# ProProject_3StepperShield_2024-04-21.net
KiCad netlist of a schematic drawn in EasyEDA Pro
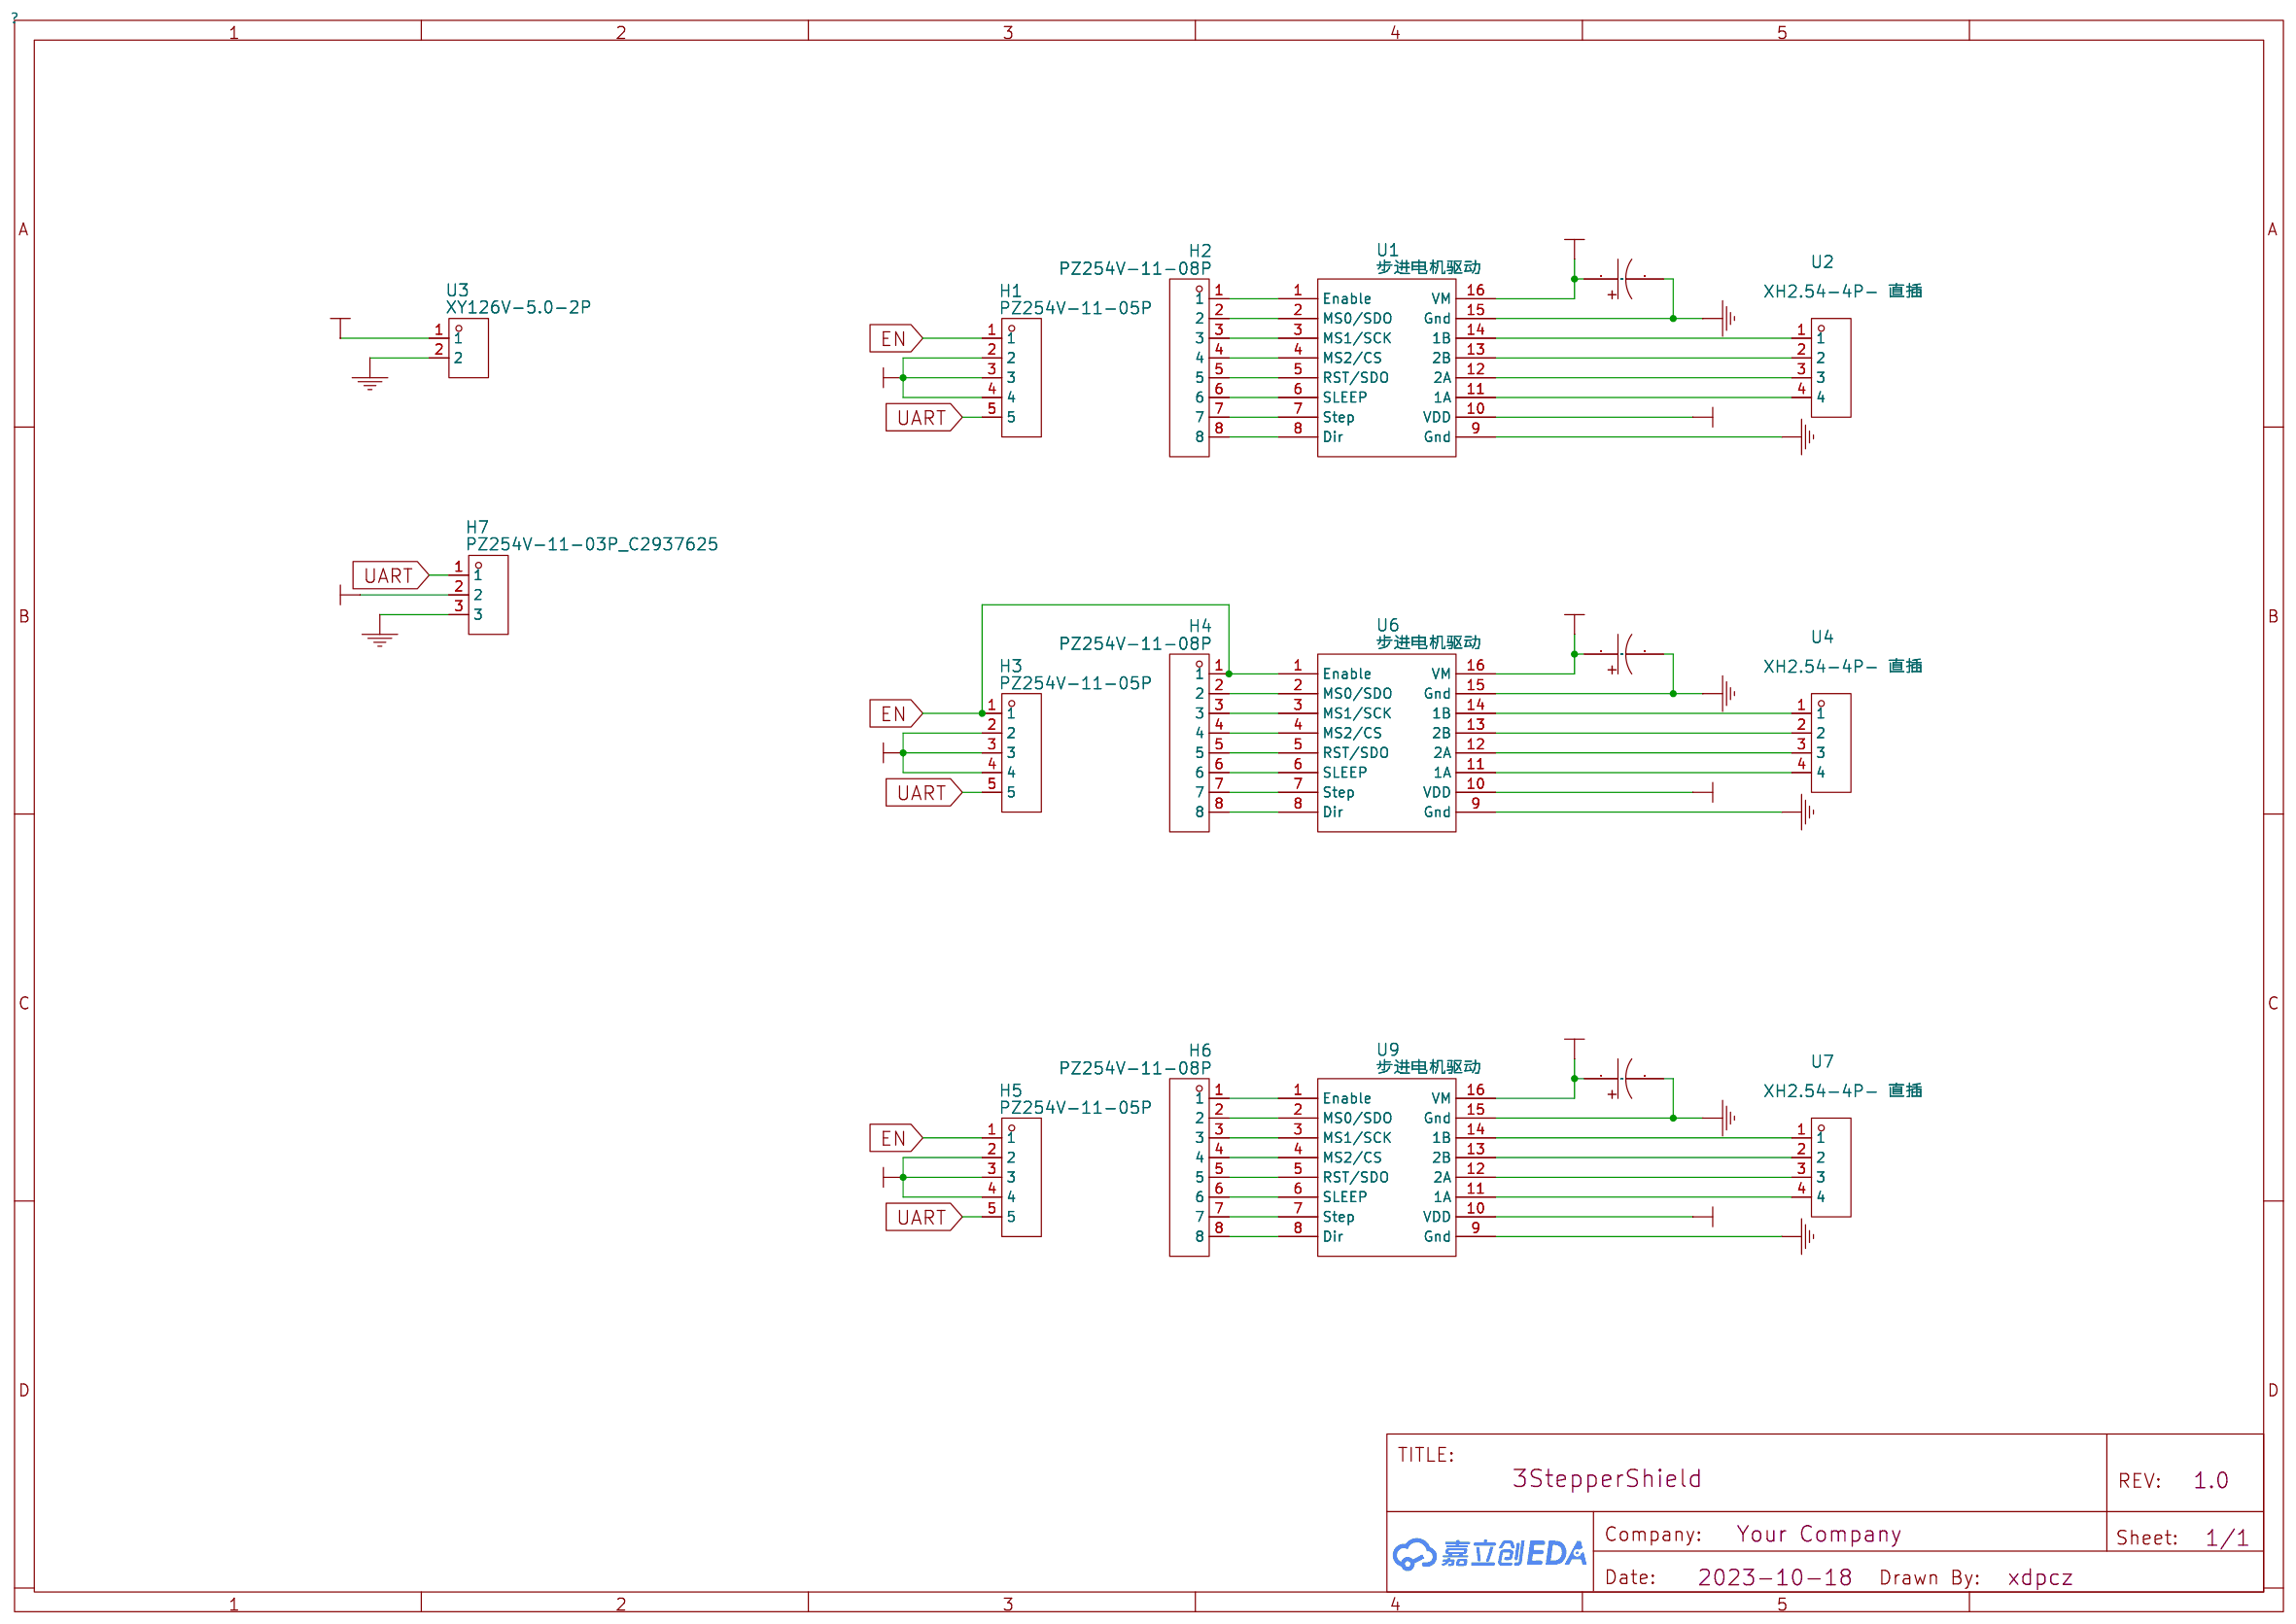
[diagram p0: schematic sheet]

(export (version "E")
  (design (tool "Eeschema 10.0.6"))
  (components
    (comp (ref "H1")
      (value "PZ254V-11-05P")
      (footprint "easyedapro:HDR-TH_5P-P2.54-V-M")
      (fields (field (name "Manufacturer") "XFCN(兴飞)"))
      (libsource (lib "easyedapro") (part "PZ254V-11-05P"))
    )
    (comp (ref "H2")
      (value "PZ254V-11-08P")
      (footprint "easyedapro:HDR-TH_8P-P2.54-V-M")
      (fields (field (name "Manufacturer") "XFCN(兴飞)"))
      (libsource (lib "easyedapro") (part "PZ254V-11-08P"))
    )
    (comp (ref "H3")
      (value "PZ254V-11-05P")
      (footprint "easyedapro:HDR-TH_5P-P2.54-V-M")
      (fields (field (name "Manufacturer") "XFCN(兴飞)"))
      (libsource (lib "easyedapro") (part "PZ254V-11-05P"))
    )
    (comp (ref "H4")
      (value "PZ254V-11-08P")
      (footprint "easyedapro:HDR-TH_8P-P2.54-V-M")
      (fields (field (name "Manufacturer") "XFCN(兴飞)"))
      (libsource (lib "easyedapro") (part "PZ254V-11-08P"))
    )
    (comp (ref "H5")
      (value "PZ254V-11-05P")
      (footprint "easyedapro:HDR-TH_5P-P2.54-V-M")
      (fields (field (name "Manufacturer") "XFCN(兴飞)"))
      (libsource (lib "easyedapro") (part "PZ254V-11-05P"))
    )
    (comp (ref "H6")
      (value "PZ254V-11-08P")
      (footprint "easyedapro:HDR-TH_8P-P2.54-V-M")
      (fields (field (name "Manufacturer") "XFCN(兴飞)"))
      (libsource (lib "easyedapro") (part "PZ254V-11-08P"))
    )
    (comp (ref "H7")
      (value "PZ254V-11-03P_C2937625")
      (footprint "easyedapro:HDR-TH_3P-P2.54-V-M")
      (fields (field (name "Manufacturer Part") "PZ254V-11-03P") (field (name "Manufacturer") "XFCN(兴飞)"))
      (libsource (lib "easyedapro") (part "PZ254V-11-03P_C2937625"))
    )
    (comp (ref "U1")
      (value "步进电机驱动")
      (footprint "easyedapro:TMC2209N_D")
      (libsource (lib "easyedapro") (part "步进电机驱动"))
    )
    (comp (ref "U2")
      (value "XH2.54-4P- 直插")
      (footprint "easyedapro:CONN-TH_4P-P2.50-XH2.54-4P")
      (libsource (lib "easyedapro") (part "XH2.54-4P- 直插"))
    )
    (comp (ref "U3")
      (value "XY126V-5.0-2P")
      (footprint "easyedapro:CONN-TH_XY126V-5.0-2P")
      (fields (field (name "Manufacturer") "XINLAIYA(新莱亚)"))
      (libsource (lib "easyedapro") (part "XY126V-5.0-2P"))
    )
    (comp (ref "U4")
      (value "XH2.54-4P- 直插")
      (footprint "easyedapro:CONN-TH_4P-P2.50-XH2.54-4P")
      (libsource (lib "easyedapro") (part "XH2.54-4P- 直插"))
    )
    (comp (ref "U5")
      (value "贴片铝电解电容100UF,20%,35V,6.3*7.7")
      (footprint "easyedapro:CAP-SMD_BD6.3-L6.6-W6.6-LS7.4-FD")
      (fields (field (name "Manufacturer Part") "贴片铝电解电容100uF,20%,35V,6.3*7.7"))
      (libsource (lib "easyedapro") (part "贴片铝电解电容100UF,20%,35V,6.3*7.7"))
    )
    (comp (ref "U6")
      (value "步进电机驱动")
      (footprint "easyedapro:TMC2209N_D")
      (libsource (lib "easyedapro") (part "步进电机驱动"))
    )
    (comp (ref "U7")
      (value "XH2.54-4P- 直插")
      (footprint "easyedapro:CONN-TH_4P-P2.50-XH2.54-4P")
      (libsource (lib "easyedapro") (part "XH2.54-4P- 直插"))
    )
    (comp (ref "U8")
      (value "贴片铝电解电容100UF,20%,35V,6.3*7.7")
      (footprint "easyedapro:CAP-SMD_BD6.3-L6.6-W6.6-LS7.4-FD")
      (fields (field (name "Manufacturer Part") "贴片铝电解电容100uF,20%,35V,6.3*7.7"))
      (libsource (lib "easyedapro") (part "贴片铝电解电容100UF,20%,35V,6.3*7.7"))
    )
    (comp (ref "U9")
      (value "步进电机驱动")
      (footprint "easyedapro:TMC2209N_D")
      (libsource (lib "easyedapro") (part "步进电机驱动"))
    )
    (comp (ref "U13")
      (value "贴片铝电解电容100UF,20%,35V,6.3*7.7")
      (footprint "easyedapro:CAP-SMD_BD6.3-L6.6-W6.6-LS7.4-FD")
      (fields (field (name "Manufacturer Part") "贴片铝电解电容100uF,20%,35V,6.3*7.7"))
      (libsource (lib "easyedapro") (part "贴片铝电解电容100UF,20%,35V,6.3*7.7"))
    )
  )
  (nets
    (net (code "1") (name "EN") (class "Default")
      (node (ref "H1") (pin "1") (pinfunction "1_1") (pintype "input"))
      (node (ref "H3") (pin "1") (pinfunction "1_1") (pintype "input"))
      (node (ref "H4") (pin "1") (pinfunction "1_1") (pintype "input"))
      (node (ref "H5") (pin "1") (pinfunction "1_1") (pintype "input"))
      (node (ref "U6") (pin "1") (pinfunction "Enable_1") (pintype "input"))
    )
    (net (code "2") (name "GND") (class "Default")
      (node (ref "H7") (pin "3") (pinfunction "3_3") (pintype "input"))
      (node (ref "U1") (pin "15") (pinfunction "Gnd_15") (pintype "input"))
      (node (ref "U1") (pin "9") (pinfunction "Gnd_9") (pintype "input"))
      (node (ref "U13") (pin "2") (pinfunction "2_2") (pintype "input"))
      (node (ref "U3") (pin "2") (pinfunction "2_2") (pintype "input"))
      (node (ref "U5") (pin "2") (pinfunction "2_2") (pintype "input"))
      (node (ref "U6") (pin "15") (pinfunction "Gnd_15") (pintype "input"))
      (node (ref "U6") (pin "9") (pinfunction "Gnd_9") (pintype "input"))
      (node (ref "U8") (pin "2") (pinfunction "2_2") (pintype "input"))
      (node (ref "U9") (pin "15") (pinfunction "Gnd_15") (pintype "input"))
      (node (ref "U9") (pin "9") (pinfunction "Gnd_9") (pintype "input"))
    )
    (net (code "3") (name "Net-(U1-1A)") (class "Default")
      (node (ref "U1") (pin "11") (pinfunction "1A_11") (pintype "input"))
      (node (ref "U2") (pin "4") (pinfunction "4_4") (pintype "input"))
    )
    (net (code "4") (name "Net-(U1-1B)") (class "Default")
      (node (ref "U1") (pin "14") (pinfunction "1B_14") (pintype "input"))
      (node (ref "U2") (pin "1") (pinfunction "1_1") (pintype "input"))
    )
    (net (code "5") (name "Net-(U1-2A)") (class "Default")
      (node (ref "U1") (pin "12") (pinfunction "2A_12") (pintype "input"))
      (node (ref "U2") (pin "3") (pinfunction "3_3") (pintype "input"))
    )
    (net (code "6") (name "Net-(U1-2B)") (class "Default")
      (node (ref "U1") (pin "13") (pinfunction "2B_13") (pintype "input"))
      (node (ref "U2") (pin "2") (pinfunction "2_2") (pintype "input"))
    )
    (net (code "7") (name "Net-(U1-Dir)") (class "Default")
      (node (ref "H2") (pin "8") (pinfunction "8_8") (pintype "input"))
      (node (ref "U1") (pin "8") (pinfunction "Dir_8") (pintype "input"))
    )
    (net (code "8") (name "Net-(U1-Enable)") (class "Default")
      (node (ref "H2") (pin "1") (pinfunction "1_1") (pintype "input"))
      (node (ref "U1") (pin "1") (pinfunction "Enable_1") (pintype "input"))
    )
    (net (code "9") (name "Net-(U1-MS0{slash}SDO)") (class "Default")
      (node (ref "H2") (pin "2") (pinfunction "2_2") (pintype "input"))
      (node (ref "U1") (pin "2") (pinfunction "MS0/SDO_2") (pintype "input"))
    )
    (net (code "10") (name "Net-(U1-MS1{slash}SCK)") (class "Default")
      (node (ref "H2") (pin "3") (pinfunction "3_3") (pintype "input"))
      (node (ref "U1") (pin "3") (pinfunction "MS1/SCK_3") (pintype "input"))
    )
    (net (code "11") (name "Net-(U1-MS2{slash}CS)") (class "Default")
      (node (ref "H2") (pin "4") (pinfunction "4_4") (pintype "input"))
      (node (ref "U1") (pin "4") (pinfunction "MS2/CS_4") (pintype "input"))
    )
    (net (code "12") (name "Net-(U1-RST{slash}SDO)") (class "Default")
      (node (ref "H2") (pin "5") (pinfunction "5_5") (pintype "input"))
      (node (ref "U1") (pin "5") (pinfunction "RST/SDO_5") (pintype "input"))
    )
    (net (code "13") (name "Net-(U1-SLEEP)") (class "Default")
      (node (ref "H2") (pin "6") (pinfunction "6_6") (pintype "input"))
      (node (ref "U1") (pin "6") (pinfunction "SLEEP_6") (pintype "input"))
    )
    (net (code "14") (name "Net-(U1-Step)") (class "Default")
      (node (ref "H2") (pin "7") (pinfunction "7_7") (pintype "input"))
      (node (ref "U1") (pin "7") (pinfunction "Step_7") (pintype "input"))
    )
    (net (code "15") (name "Net-(U6-1A)") (class "Default")
      (node (ref "U4") (pin "4") (pinfunction "4_4") (pintype "input"))
      (node (ref "U6") (pin "11") (pinfunction "1A_11") (pintype "input"))
    )
    (net (code "16") (name "Net-(U6-1B)") (class "Default")
      (node (ref "U4") (pin "1") (pinfunction "1_1") (pintype "input"))
      (node (ref "U6") (pin "14") (pinfunction "1B_14") (pintype "input"))
    )
    (net (code "17") (name "Net-(U6-2A)") (class "Default")
      (node (ref "U4") (pin "3") (pinfunction "3_3") (pintype "input"))
      (node (ref "U6") (pin "12") (pinfunction "2A_12") (pintype "input"))
    )
    (net (code "18") (name "Net-(U6-2B)") (class "Default")
      (node (ref "U4") (pin "2") (pinfunction "2_2") (pintype "input"))
      (node (ref "U6") (pin "13") (pinfunction "2B_13") (pintype "input"))
    )
    (net (code "19") (name "Net-(U6-Dir)") (class "Default")
      (node (ref "H4") (pin "8") (pinfunction "8_8") (pintype "input"))
      (node (ref "U6") (pin "8") (pinfunction "Dir_8") (pintype "input"))
    )
    (net (code "20") (name "Net-(U6-MS0{slash}SDO)") (class "Default")
      (node (ref "H4") (pin "2") (pinfunction "2_2") (pintype "input"))
      (node (ref "U6") (pin "2") (pinfunction "MS0/SDO_2") (pintype "input"))
    )
    (net (code "21") (name "Net-(U6-MS1{slash}SCK)") (class "Default")
      (node (ref "H4") (pin "3") (pinfunction "3_3") (pintype "input"))
      (node (ref "U6") (pin "3") (pinfunction "MS1/SCK_3") (pintype "input"))
    )
    (net (code "22") (name "Net-(U6-MS2{slash}CS)") (class "Default")
      (node (ref "H4") (pin "4") (pinfunction "4_4") (pintype "input"))
      (node (ref "U6") (pin "4") (pinfunction "MS2/CS_4") (pintype "input"))
    )
    (net (code "23") (name "Net-(U6-RST{slash}SDO)") (class "Default")
      (node (ref "H4") (pin "5") (pinfunction "5_5") (pintype "input"))
      (node (ref "U6") (pin "5") (pinfunction "RST/SDO_5") (pintype "input"))
    )
    (net (code "24") (name "Net-(U6-SLEEP)") (class "Default")
      (node (ref "H4") (pin "6") (pinfunction "6_6") (pintype "input"))
      (node (ref "U6") (pin "6") (pinfunction "SLEEP_6") (pintype "input"))
    )
    (net (code "25") (name "Net-(U6-Step)") (class "Default")
      (node (ref "H4") (pin "7") (pinfunction "7_7") (pintype "input"))
      (node (ref "U6") (pin "7") (pinfunction "Step_7") (pintype "input"))
    )
    (net (code "26") (name "Net-(U9-1A)") (class "Default")
      (node (ref "U7") (pin "4") (pinfunction "4_4") (pintype "input"))
      (node (ref "U9") (pin "11") (pinfunction "1A_11") (pintype "input"))
    )
    (net (code "27") (name "Net-(U9-1B)") (class "Default")
      (node (ref "U7") (pin "1") (pinfunction "1_1") (pintype "input"))
      (node (ref "U9") (pin "14") (pinfunction "1B_14") (pintype "input"))
    )
    (net (code "28") (name "Net-(U9-2A)") (class "Default")
      (node (ref "U7") (pin "3") (pinfunction "3_3") (pintype "input"))
      (node (ref "U9") (pin "12") (pinfunction "2A_12") (pintype "input"))
    )
    (net (code "29") (name "Net-(U9-2B)") (class "Default")
      (node (ref "U7") (pin "2") (pinfunction "2_2") (pintype "input"))
      (node (ref "U9") (pin "13") (pinfunction "2B_13") (pintype "input"))
    )
    (net (code "30") (name "Net-(U9-Dir)") (class "Default")
      (node (ref "H6") (pin "8") (pinfunction "8_8") (pintype "input"))
      (node (ref "U9") (pin "8") (pinfunction "Dir_8") (pintype "input"))
    )
    (net (code "31") (name "Net-(U9-Enable)") (class "Default")
      (node (ref "H6") (pin "1") (pinfunction "1_1") (pintype "input"))
      (node (ref "U9") (pin "1") (pinfunction "Enable_1") (pintype "input"))
    )
    (net (code "32") (name "Net-(U9-MS0{slash}SDO)") (class "Default")
      (node (ref "H6") (pin "2") (pinfunction "2_2") (pintype "input"))
      (node (ref "U9") (pin "2") (pinfunction "MS0/SDO_2") (pintype "input"))
    )
    (net (code "33") (name "Net-(U9-MS1{slash}SCK)") (class "Default")
      (node (ref "H6") (pin "3") (pinfunction "3_3") (pintype "input"))
      (node (ref "U9") (pin "3") (pinfunction "MS1/SCK_3") (pintype "input"))
    )
    (net (code "34") (name "Net-(U9-MS2{slash}CS)") (class "Default")
      (node (ref "H6") (pin "4") (pinfunction "4_4") (pintype "input"))
      (node (ref "U9") (pin "4") (pinfunction "MS2/CS_4") (pintype "input"))
    )
    (net (code "35") (name "Net-(U9-RST{slash}SDO)") (class "Default")
      (node (ref "H6") (pin "5") (pinfunction "5_5") (pintype "input"))
      (node (ref "U9") (pin "5") (pinfunction "RST/SDO_5") (pintype "input"))
    )
    (net (code "36") (name "Net-(U9-SLEEP)") (class "Default")
      (node (ref "H6") (pin "6") (pinfunction "6_6") (pintype "input"))
      (node (ref "U9") (pin "6") (pinfunction "SLEEP_6") (pintype "input"))
    )
    (net (code "37") (name "Net-(U9-Step)") (class "Default")
      (node (ref "H6") (pin "7") (pinfunction "7_7") (pintype "input"))
      (node (ref "U9") (pin "7") (pinfunction "Step_7") (pintype "input"))
    )
    (net (code "38") (name "UART") (class "Default")
      (node (ref "H1") (pin "5") (pinfunction "5_5") (pintype "input"))
      (node (ref "H3") (pin "5") (pinfunction "5_5") (pintype "input"))
      (node (ref "H5") (pin "5") (pinfunction "5_5") (pintype "input"))
      (node (ref "H7") (pin "1") (pinfunction "1_1") (pintype "input"))
    )
    (net (code "39") (name "VCC") (class "Default")
      (node (ref "U1") (pin "16") (pinfunction "VM_16") (pintype "input"))
      (node (ref "U13") (pin "1") (pinfunction "1_1") (pintype "input"))
      (node (ref "U3") (pin "1") (pinfunction "1_1") (pintype "input"))
      (node (ref "U5") (pin "1") (pinfunction "1_1") (pintype "input"))
      (node (ref "U6") (pin "16") (pinfunction "VM_16") (pintype "input"))
      (node (ref "U8") (pin "1") (pinfunction "1_1") (pintype "input"))
      (node (ref "U9") (pin "16") (pinfunction "VM_16") (pintype "input"))
    )
    (net (code "40") (name "VDD") (class "Default")
      (node (ref "H1") (pin "2") (pinfunction "2_2") (pintype "input"))
      (node (ref "H1") (pin "3") (pinfunction "3_3") (pintype "input"))
      (node (ref "H1") (pin "4") (pinfunction "4_4") (pintype "input"))
      (node (ref "H3") (pin "2") (pinfunction "2_2") (pintype "input"))
      (node (ref "H3") (pin "3") (pinfunction "3_3") (pintype "input"))
      (node (ref "H3") (pin "4") (pinfunction "4_4") (pintype "input"))
      (node (ref "H5") (pin "2") (pinfunction "2_2") (pintype "input"))
      (node (ref "H5") (pin "3") (pinfunction "3_3") (pintype "input"))
      (node (ref "H5") (pin "4") (pinfunction "4_4") (pintype "input"))
      (node (ref "H7") (pin "2") (pinfunction "2_2") (pintype "input"))
      (node (ref "U1") (pin "10") (pinfunction "VDD_10") (pintype "input"))
      (node (ref "U6") (pin "10") (pinfunction "VDD_10") (pintype "input"))
      (node (ref "U9") (pin "10") (pinfunction "VDD_10") (pintype "input"))
    )
  )
)
